# Aux_Power_Board_V2_1.net
KiCad netlist of a schematic drawn in EAGLE
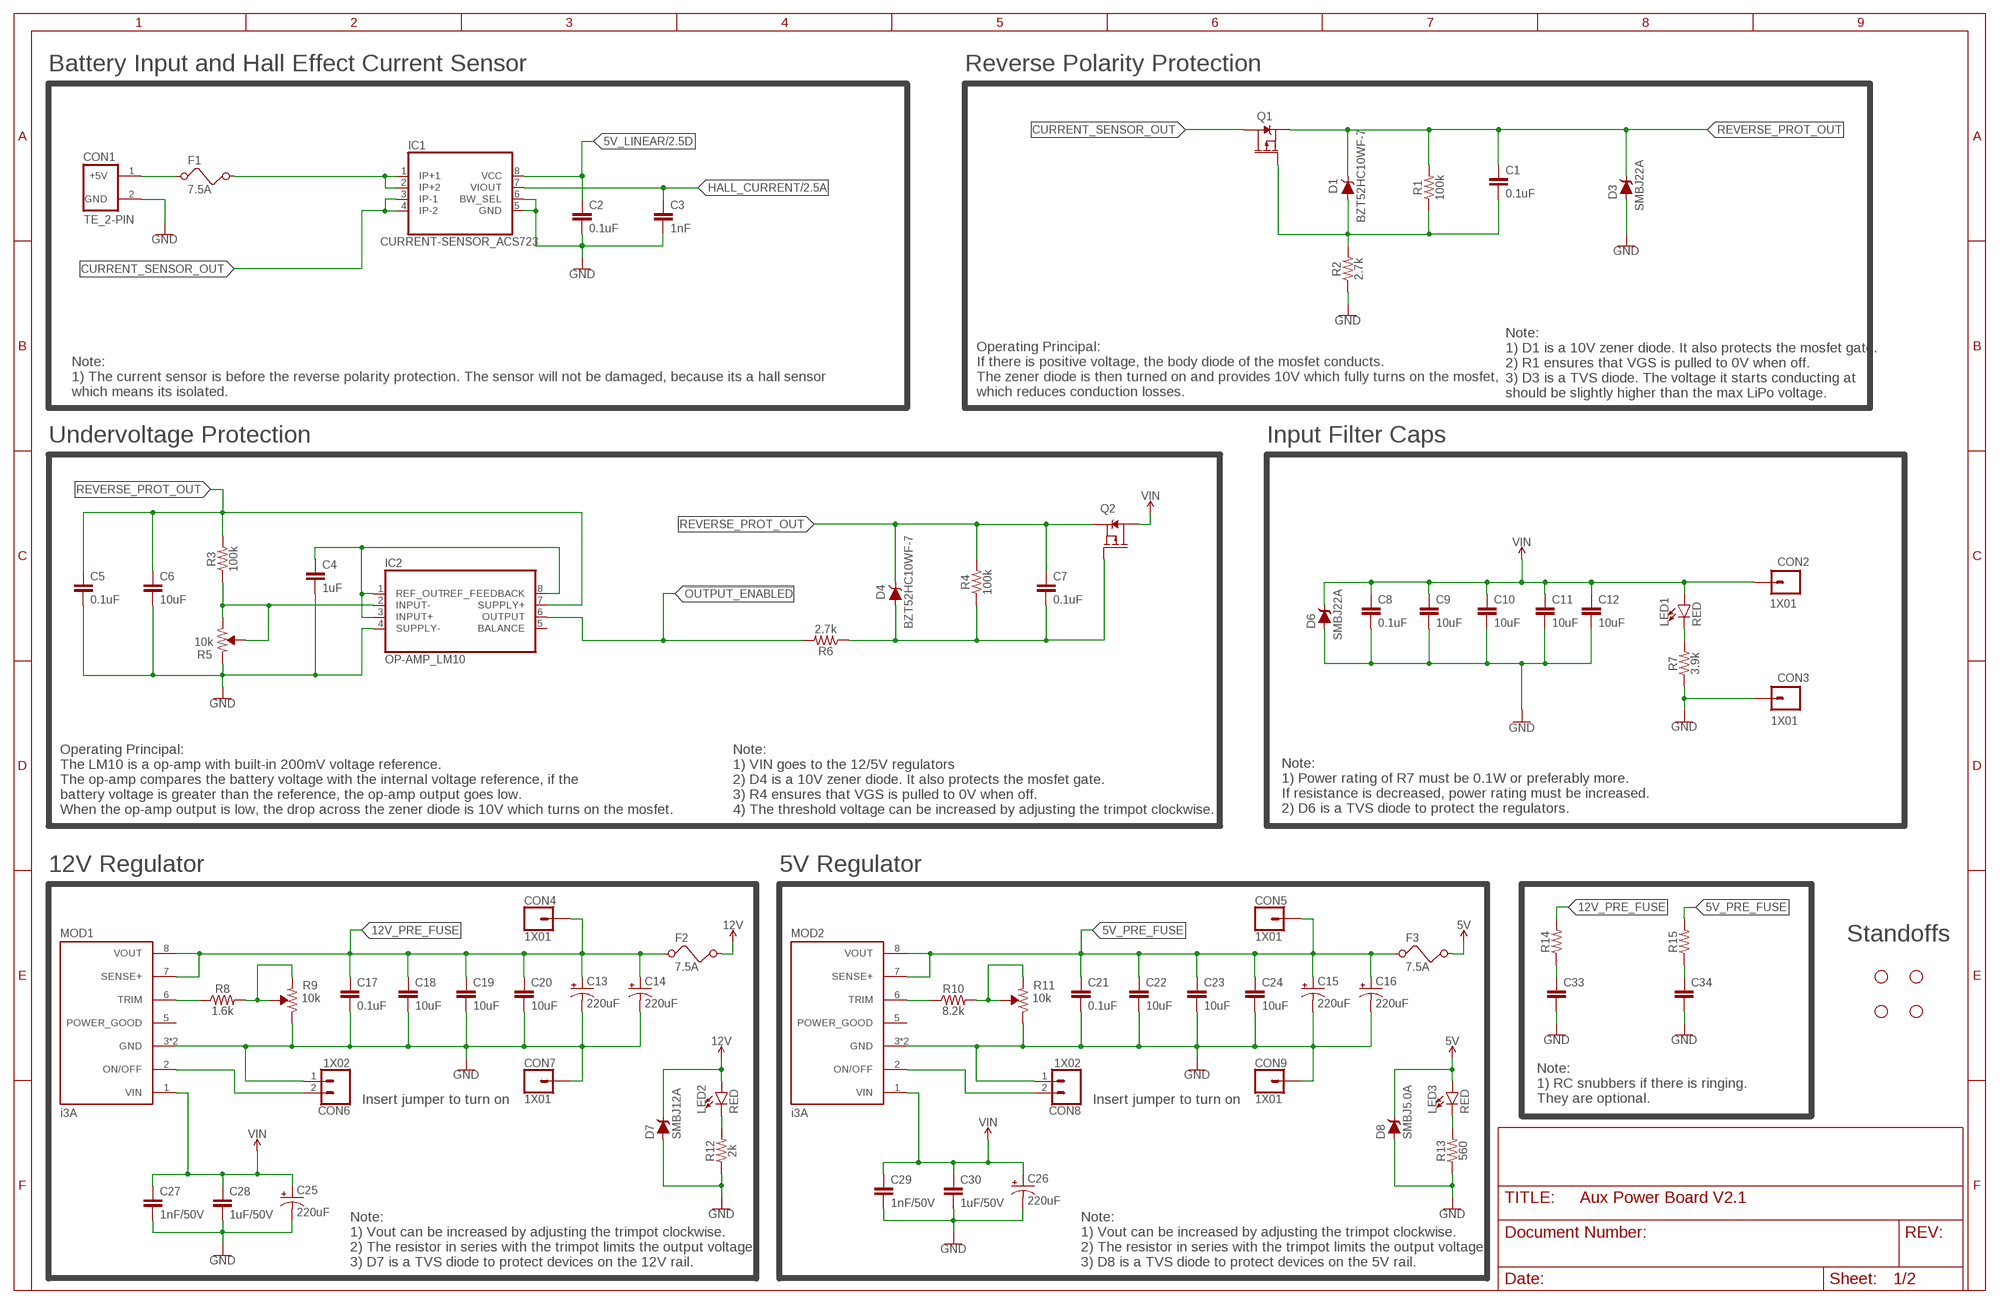
[diagram p0: schematic, sheet 1]
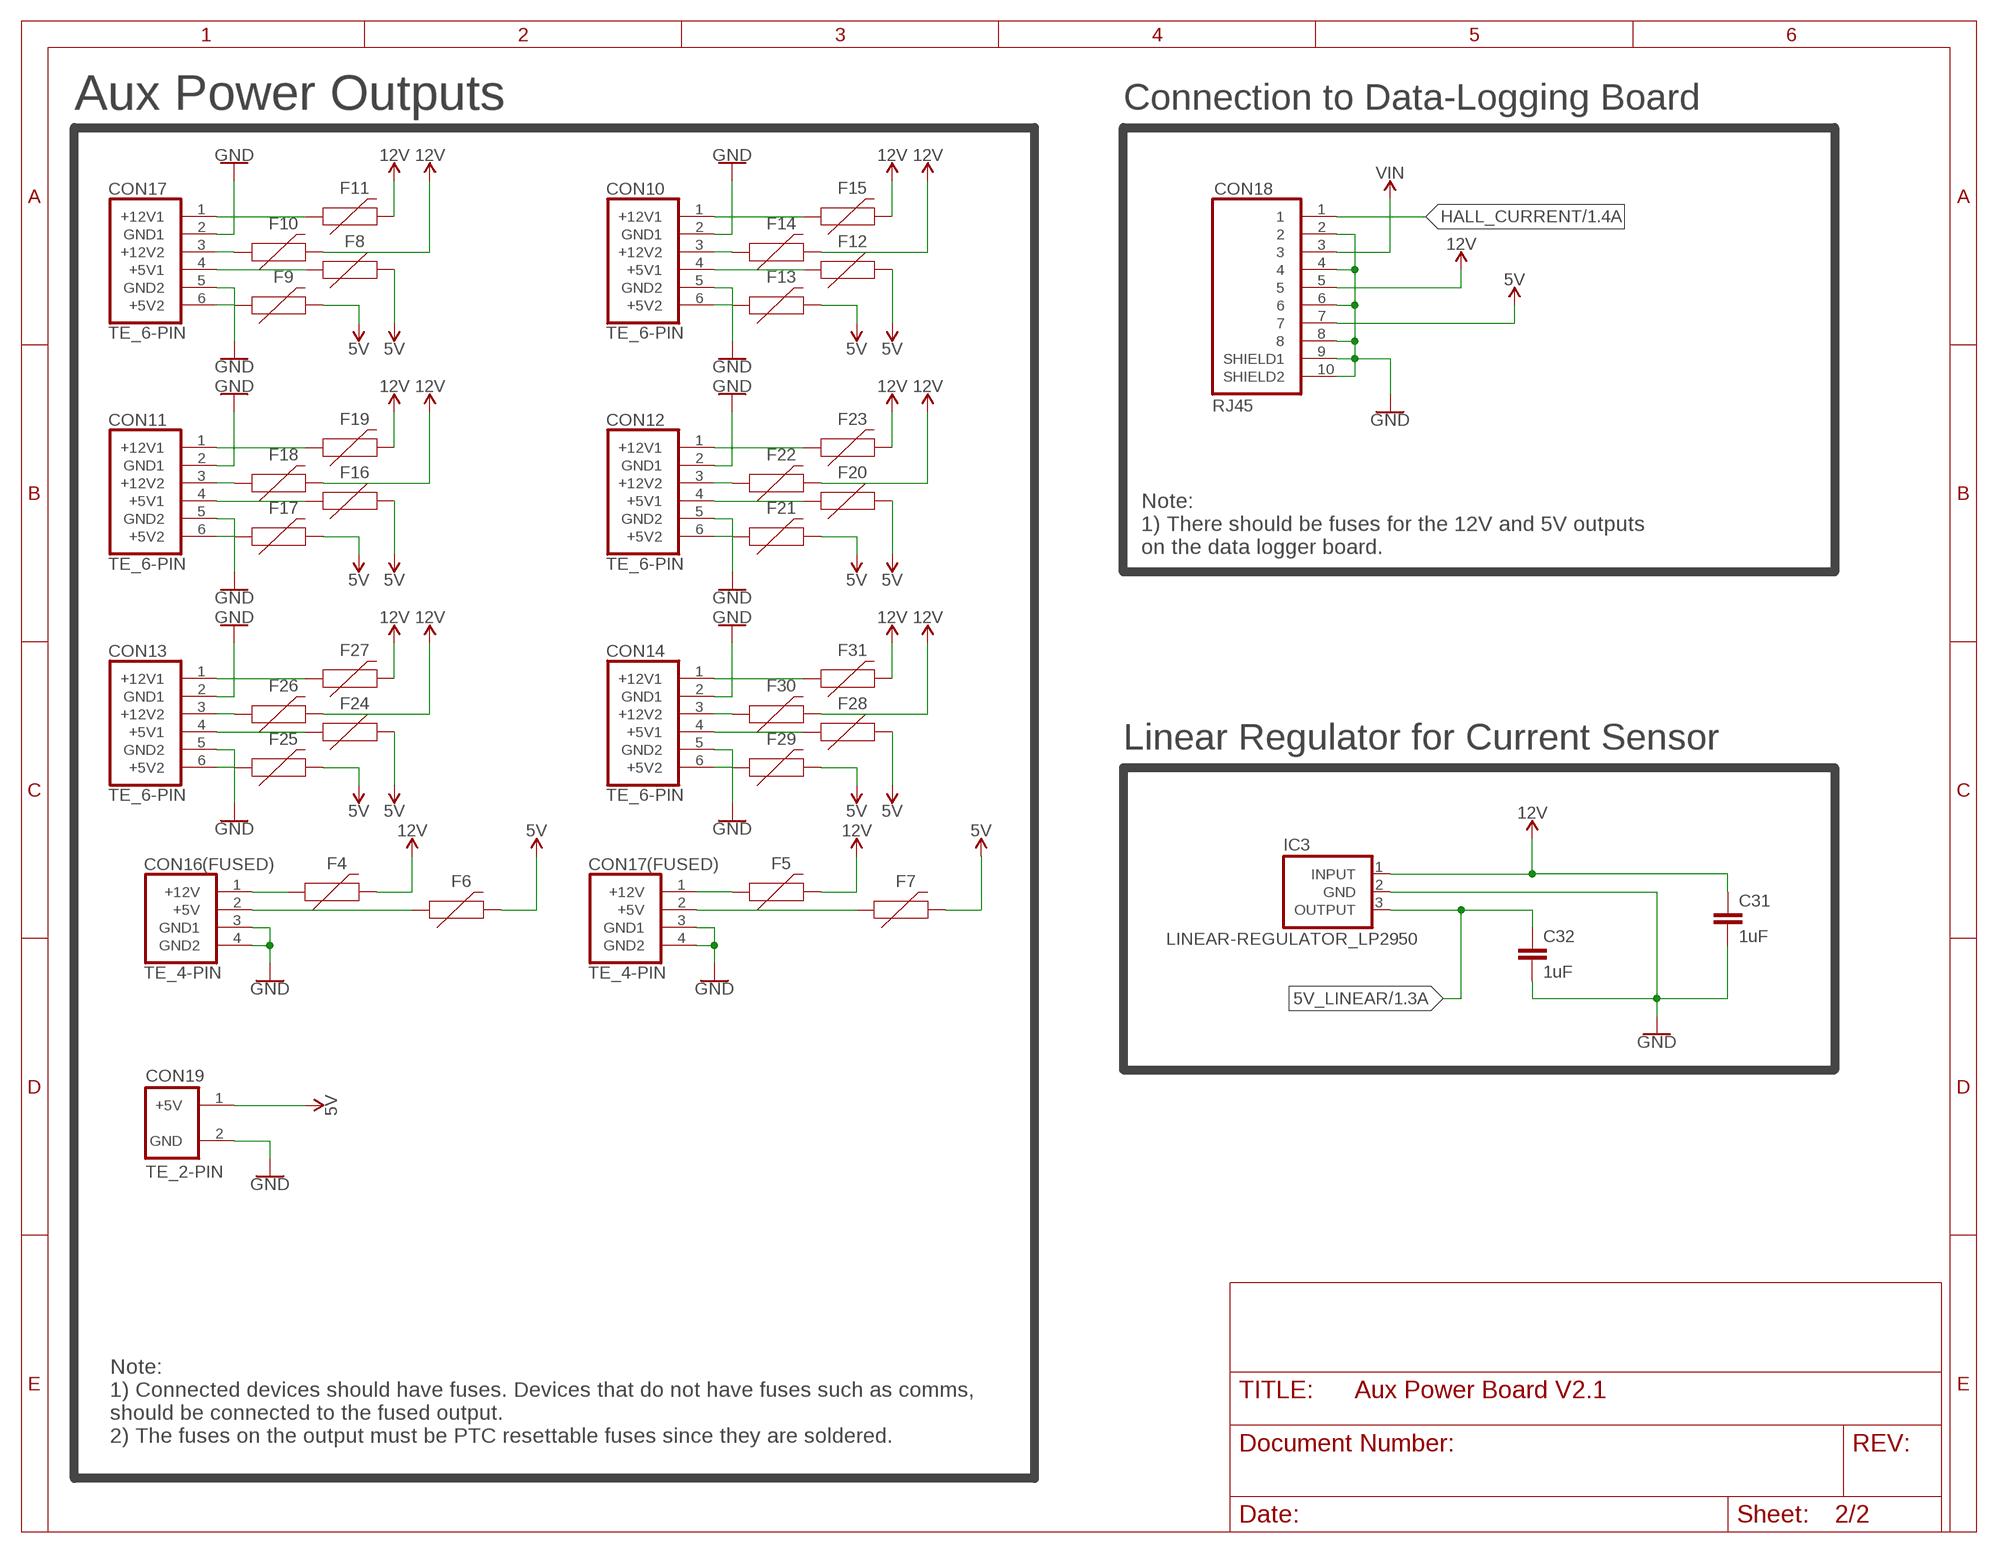
[diagram p1: schematic, sheet 2]

(export (version "E")
  (design (tool "Eeschema 10.0.6"))
  (components
    (comp (ref "C31")
      (value "1uF")
      (footprint "eagle-import:0805")
      (libsource (lib "eagle-import") (part "CAPACITOR_0805"))
    )
    (comp (ref "C32")
      (value "1uF")
      (footprint "eagle-import:0805")
      (libsource (lib "eagle-import") (part "CAPACITOR_0805"))
    )
    (comp (ref "CON10")
      (value "TE_6-PIN")
      (footprint "eagle-import:TE_6-PIN")
      (libsource (lib "eagle-import") (part "TE_6-PIN"))
    )
    (comp (ref "CON11")
      (value "TE_6-PIN")
      (footprint "eagle-import:TE_6-PIN")
      (libsource (lib "eagle-import") (part "TE_6-PIN"))
    )
    (comp (ref "CON12")
      (value "TE_6-PIN")
      (footprint "eagle-import:TE_6-PIN")
      (libsource (lib "eagle-import") (part "TE_6-PIN"))
    )
    (comp (ref "CON13")
      (value "TE_6-PIN")
      (footprint "eagle-import:TE_6-PIN")
      (libsource (lib "eagle-import") (part "TE_6-PIN"))
    )
    (comp (ref "CON14")
      (value "TE_6-PIN")
      (footprint "eagle-import:TE_6-PIN")
      (libsource (lib "eagle-import") (part "TE_6-PIN"))
    )
    (comp (ref "CON16(FUSED)")
      (value "TE_4-PIN")
      (footprint "eagle-import:TE_4-PIN")
      (libsource (lib "eagle-import") (part "TE_4-PIN"))
    )
    (comp (ref "CON17")
      (value "TE_6-PIN")
      (footprint "eagle-import:TE_6-PIN")
      (libsource (lib "eagle-import") (part "TE_6-PIN"))
    )
    (comp (ref "CON17(FUSED)")
      (value "TE_4-PIN")
      (footprint "eagle-import:TE_4-PIN")
      (libsource (lib "eagle-import") (part "TE_4-PIN"))
    )
    (comp (ref "CON18")
      (value "RJ45")
      (footprint "eagle-import:RJ45")
      (libsource (lib "eagle-import") (part "RJ45"))
    )
    (comp (ref "CON19")
      (value "TE_2-PIN")
      (footprint "eagle-import:TE_2-PIN")
      (libsource (lib "eagle-import") (part "TE_2-PIN"))
    )
    (comp (ref "F4")
      (value "FUSE_1210_RESETTABLE")
      (footprint "eagle-import:1210")
      (libsource (lib "eagle-import") (part "FUSE_1210_RESETTABLE"))
    )
    (comp (ref "F5")
      (value "FUSE_1210_RESETTABLE")
      (footprint "eagle-import:1210")
      (libsource (lib "eagle-import") (part "FUSE_1210_RESETTABLE"))
    )
    (comp (ref "F6")
      (value "FUSE_1210_RESETTABLE")
      (footprint "eagle-import:1210")
      (libsource (lib "eagle-import") (part "FUSE_1210_RESETTABLE"))
    )
    (comp (ref "F7")
      (value "FUSE_1210_RESETTABLE")
      (footprint "eagle-import:1210")
      (libsource (lib "eagle-import") (part "FUSE_1210_RESETTABLE"))
    )
    (comp (ref "F8")
      (value "FUSE_1210_RESETTABLE")
      (footprint "eagle-import:1210")
      (libsource (lib "eagle-import") (part "FUSE_1210_RESETTABLE"))
    )
    (comp (ref "F9")
      (value "FUSE_1210_RESETTABLE")
      (footprint "eagle-import:1210")
      (libsource (lib "eagle-import") (part "FUSE_1210_RESETTABLE"))
    )
    (comp (ref "F10")
      (value "FUSE_1210_RESETTABLE")
      (footprint "eagle-import:1210")
      (libsource (lib "eagle-import") (part "FUSE_1210_RESETTABLE"))
    )
    (comp (ref "F11")
      (value "FUSE_1210_RESETTABLE")
      (footprint "eagle-import:1210")
      (libsource (lib "eagle-import") (part "FUSE_1210_RESETTABLE"))
    )
    (comp (ref "F12")
      (value "FUSE_1210_RESETTABLE")
      (footprint "eagle-import:1210")
      (libsource (lib "eagle-import") (part "FUSE_1210_RESETTABLE"))
    )
    (comp (ref "F13")
      (value "FUSE_1210_RESETTABLE")
      (footprint "eagle-import:1210")
      (libsource (lib "eagle-import") (part "FUSE_1210_RESETTABLE"))
    )
    (comp (ref "F14")
      (value "FUSE_1210_RESETTABLE")
      (footprint "eagle-import:1210")
      (libsource (lib "eagle-import") (part "FUSE_1210_RESETTABLE"))
    )
    (comp (ref "F15")
      (value "FUSE_1210_RESETTABLE")
      (footprint "eagle-import:1210")
      (libsource (lib "eagle-import") (part "FUSE_1210_RESETTABLE"))
    )
    (comp (ref "F16")
      (value "FUSE_1210_RESETTABLE")
      (footprint "eagle-import:1210")
      (libsource (lib "eagle-import") (part "FUSE_1210_RESETTABLE"))
    )
    (comp (ref "F17")
      (value "FUSE_1210_RESETTABLE")
      (footprint "eagle-import:1210")
      (libsource (lib "eagle-import") (part "FUSE_1210_RESETTABLE"))
    )
    (comp (ref "F18")
      (value "FUSE_1210_RESETTABLE")
      (footprint "eagle-import:1210")
      (libsource (lib "eagle-import") (part "FUSE_1210_RESETTABLE"))
    )
    (comp (ref "F19")
      (value "FUSE_1210_RESETTABLE")
      (footprint "eagle-import:1210")
      (libsource (lib "eagle-import") (part "FUSE_1210_RESETTABLE"))
    )
    (comp (ref "F20")
      (value "FUSE_1210_RESETTABLE")
      (footprint "eagle-import:1210")
      (libsource (lib "eagle-import") (part "FUSE_1210_RESETTABLE"))
    )
    (comp (ref "F21")
      (value "FUSE_1210_RESETTABLE")
      (footprint "eagle-import:1210")
      (libsource (lib "eagle-import") (part "FUSE_1210_RESETTABLE"))
    )
    (comp (ref "F22")
      (value "FUSE_1210_RESETTABLE")
      (footprint "eagle-import:1210")
      (libsource (lib "eagle-import") (part "FUSE_1210_RESETTABLE"))
    )
    (comp (ref "F23")
      (value "FUSE_1210_RESETTABLE")
      (footprint "eagle-import:1210")
      (libsource (lib "eagle-import") (part "FUSE_1210_RESETTABLE"))
    )
    (comp (ref "F24")
      (value "FUSE_1210_RESETTABLE")
      (footprint "eagle-import:1210")
      (libsource (lib "eagle-import") (part "FUSE_1210_RESETTABLE"))
    )
    (comp (ref "F25")
      (value "FUSE_1210_RESETTABLE")
      (footprint "eagle-import:1210")
      (libsource (lib "eagle-import") (part "FUSE_1210_RESETTABLE"))
    )
    (comp (ref "F26")
      (value "FUSE_1210_RESETTABLE")
      (footprint "eagle-import:1210")
      (libsource (lib "eagle-import") (part "FUSE_1210_RESETTABLE"))
    )
    (comp (ref "F27")
      (value "FUSE_1210_RESETTABLE")
      (footprint "eagle-import:1210")
      (libsource (lib "eagle-import") (part "FUSE_1210_RESETTABLE"))
    )
    (comp (ref "F28")
      (value "FUSE_1210_RESETTABLE")
      (footprint "eagle-import:1210")
      (libsource (lib "eagle-import") (part "FUSE_1210_RESETTABLE"))
    )
    (comp (ref "F29")
      (value "FUSE_1210_RESETTABLE")
      (footprint "eagle-import:1210")
      (libsource (lib "eagle-import") (part "FUSE_1210_RESETTABLE"))
    )
    (comp (ref "F30")
      (value "FUSE_1210_RESETTABLE")
      (footprint "eagle-import:1210")
      (libsource (lib "eagle-import") (part "FUSE_1210_RESETTABLE"))
    )
    (comp (ref "F31")
      (value "FUSE_1210_RESETTABLE")
      (footprint "eagle-import:1210")
      (libsource (lib "eagle-import") (part "FUSE_1210_RESETTABLE"))
    )
    (comp (ref "IC3")
      (value "LINEAR-REGULATOR_LP2950")
      (footprint "eagle-import:TO92")
      (libsource (lib "eagle-import") (part "LINEAR-REGULATOR_LP2950"))
    )
    (comp (ref "C1")
      (value "0.1uF")
      (footprint "eagle-import:0805")
      (libsource (lib "eagle-import") (part "CAPACITOR_0805"))
    )
    (comp (ref "C2")
      (value "0.1uF")
      (footprint "eagle-import:0805")
      (libsource (lib "eagle-import") (part "CAPACITOR_0805"))
    )
    (comp (ref "C3")
      (value "1nF")
      (footprint "eagle-import:0805")
      (libsource (lib "eagle-import") (part "CAPACITOR_0805"))
    )
    (comp (ref "C4")
      (value "1uF")
      (footprint "eagle-import:0805")
      (libsource (lib "eagle-import") (part "CAPACITOR_0805"))
    )
    (comp (ref "C5")
      (value "0.1uF")
      (footprint "eagle-import:0805")
      (libsource (lib "eagle-import") (part "CAPACITOR_0805"))
    )
    (comp (ref "C6")
      (value "10uF")
      (footprint "eagle-import:1210")
      (libsource (lib "eagle-import") (part "CAPACITOR_1210"))
    )
    (comp (ref "C7")
      (value "0.1uF")
      (footprint "eagle-import:0805")
      (libsource (lib "eagle-import") (part "CAPACITOR_0805"))
    )
    (comp (ref "C8")
      (value "0.1uF")
      (footprint "eagle-import:0805")
      (libsource (lib "eagle-import") (part "CAPACITOR_0805"))
    )
    (comp (ref "C9")
      (value "10uF")
      (footprint "eagle-import:1210")
      (libsource (lib "eagle-import") (part "CAPACITOR_1210"))
    )
    (comp (ref "C10")
      (value "10uF")
      (footprint "eagle-import:1210")
      (libsource (lib "eagle-import") (part "CAPACITOR_1210"))
    )
    (comp (ref "C11")
      (value "10uF")
      (footprint "eagle-import:1210")
      (libsource (lib "eagle-import") (part "CAPACITOR_1210"))
    )
    (comp (ref "C12")
      (value "10uF")
      (footprint "eagle-import:1210")
      (libsource (lib "eagle-import") (part "CAPACITOR_1210"))
    )
    (comp (ref "C13")
      (value "220uF")
      (footprint "eagle-import:CAPACITOR_220UF_63V")
      (libsource (lib "eagle-import") (part "CAPACITOR_ELECTROLYTIC_220UF"))
    )
    (comp (ref "C14")
      (value "220uF")
      (footprint "eagle-import:CAPACITOR_220UF_63V")
      (libsource (lib "eagle-import") (part "CAPACITOR_ELECTROLYTIC_220UF"))
    )
    (comp (ref "C15")
      (value "220uF")
      (footprint "eagle-import:CAPACITOR_220UF_63V")
      (libsource (lib "eagle-import") (part "CAPACITOR_ELECTROLYTIC_220UF"))
    )
    (comp (ref "C16")
      (value "220uF")
      (footprint "eagle-import:CAPACITOR_220UF_63V")
      (libsource (lib "eagle-import") (part "CAPACITOR_ELECTROLYTIC_220UF"))
    )
    (comp (ref "C17")
      (value "0.1uF")
      (footprint "eagle-import:0805")
      (libsource (lib "eagle-import") (part "CAPACITOR_0805"))
    )
    (comp (ref "C18")
      (value "10uF")
      (footprint "eagle-import:0805")
      (libsource (lib "eagle-import") (part "CAPACITOR_0805"))
    )
    (comp (ref "C19")
      (value "10uF")
      (footprint "eagle-import:0805")
      (libsource (lib "eagle-import") (part "CAPACITOR_0805"))
    )
    (comp (ref "C20")
      (value "10uF")
      (footprint "eagle-import:0805")
      (libsource (lib "eagle-import") (part "CAPACITOR_0805"))
    )
    (comp (ref "C21")
      (value "0.1uF")
      (footprint "eagle-import:0805")
      (libsource (lib "eagle-import") (part "CAPACITOR_0805"))
    )
    (comp (ref "C22")
      (value "10uF")
      (footprint "eagle-import:0805")
      (libsource (lib "eagle-import") (part "CAPACITOR_0805"))
    )
    (comp (ref "C23")
      (value "10uF")
      (footprint "eagle-import:0805")
      (libsource (lib "eagle-import") (part "CAPACITOR_0805"))
    )
    (comp (ref "C24")
      (value "10uF")
      (footprint "eagle-import:0805")
      (libsource (lib "eagle-import") (part "CAPACITOR_0805"))
    )
    (comp (ref "C25")
      (value "220uF")
      (footprint "eagle-import:CAPACITOR_220UF_63V")
      (libsource (lib "eagle-import") (part "CAPACITOR_ELECTROLYTIC_220UF"))
    )
    (comp (ref "C26")
      (value "220uF")
      (footprint "eagle-import:CAPACITOR_220UF_63V")
      (libsource (lib "eagle-import") (part "CAPACITOR_ELECTROLYTIC_220UF"))
    )
    (comp (ref "C27")
      (value "1nF/50V")
      (footprint "eagle-import:0805")
      (libsource (lib "eagle-import") (part "CAPACITOR_0805"))
    )
    (comp (ref "C28")
      (value "1uF/50V")
      (footprint "eagle-import:0805")
      (libsource (lib "eagle-import") (part "CAPACITOR_0805"))
    )
    (comp (ref "C29")
      (value "1nF/50V")
      (footprint "eagle-import:0805")
      (libsource (lib "eagle-import") (part "CAPACITOR_0805"))
    )
    (comp (ref "C30")
      (value "1uF/50V")
      (footprint "eagle-import:0805")
      (libsource (lib "eagle-import") (part "CAPACITOR_0805"))
    )
    (comp (ref "C33")
      (value "CAPACITOR_0805")
      (footprint "eagle-import:0805")
      (libsource (lib "eagle-import") (part "CAPACITOR_0805"))
    )
    (comp (ref "C34")
      (value "CAPACITOR_0805")
      (footprint "eagle-import:0805")
      (libsource (lib "eagle-import") (part "CAPACITOR_0805"))
    )
    (comp (ref "CON1")
      (value "TE_2-PIN")
      (footprint "eagle-import:TE_2-PIN")
      (libsource (lib "eagle-import") (part "TE_2-PIN"))
    )
    (comp (ref "CON2")
      (value "1X01")
      (footprint "eagle-import:1X01")
      (libsource (lib "eagle-import") (part "1X01"))
    )
    (comp (ref "CON3")
      (value "1X01")
      (footprint "eagle-import:1X01")
      (libsource (lib "eagle-import") (part "1X01"))
    )
    (comp (ref "CON4")
      (value "1X01")
      (footprint "eagle-import:1X01")
      (libsource (lib "eagle-import") (part "1X01"))
    )
    (comp (ref "CON5")
      (value "1X01")
      (footprint "eagle-import:1X01")
      (libsource (lib "eagle-import") (part "1X01"))
    )
    (comp (ref "CON6")
      (value "1X02")
      (footprint "eagle-import:1X02")
      (libsource (lib "eagle-import") (part "1X02"))
    )
    (comp (ref "CON7")
      (value "1X01")
      (footprint "eagle-import:1X01")
      (libsource (lib "eagle-import") (part "1X01"))
    )
    (comp (ref "CON8")
      (value "1X02")
      (footprint "eagle-import:1X02")
      (libsource (lib "eagle-import") (part "1X02"))
    )
    (comp (ref "CON9")
      (value "1X01")
      (footprint "eagle-import:1X01")
      (libsource (lib "eagle-import") (part "1X01"))
    )
    (comp (ref "D1")
      (value "BZT52HC10WF-7")
      (footprint "eagle-import:SOD123FL")
      (libsource (lib "eagle-import") (part "DIODE_ZENER_SOD123F"))
    )
    (comp (ref "D3")
      (value "SMBJ22A")
      (footprint "eagle-import:DO214AA")
      (libsource (lib "eagle-import") (part "DIODE_TVS_UNI_DO-214AA"))
    )
    (comp (ref "D4")
      (value "BZT52HC10WF-7")
      (footprint "eagle-import:SOD123FL")
      (libsource (lib "eagle-import") (part "DIODE_ZENER_SOD123F"))
    )
    (comp (ref "D6")
      (value "SMBJ22A")
      (footprint "eagle-import:DO214AA")
      (libsource (lib "eagle-import") (part "DIODE_TVS_UNI_DO-214AA"))
    )
    (comp (ref "D7")
      (value "SMBJ12A")
      (footprint "eagle-import:DO214AA")
      (libsource (lib "eagle-import") (part "DIODE_TVS_UNI_DO-214AA"))
    )
    (comp (ref "D8")
      (value "SMBJ5.0A")
      (footprint "eagle-import:DO214AA")
      (libsource (lib "eagle-import") (part "DIODE_TVS_UNI_DO-214AA"))
    )
    (comp (ref "F1")
      (value "7.5A")
      (footprint "eagle-import:FUSEHOLDER_VERTICAL")
      (libsource (lib "eagle-import") (part "FUSEHOLDER_VERTICAL"))
    )
    (comp (ref "F2")
      (value "7.5A")
      (footprint "eagle-import:FUSEHOLDER_VERTICAL")
      (libsource (lib "eagle-import") (part "FUSEHOLDER_VERTICAL"))
    )
    (comp (ref "F3")
      (value "7.5A")
      (footprint "eagle-import:FUSEHOLDER_VERTICAL")
      (libsource (lib "eagle-import") (part "FUSEHOLDER_VERTICAL"))
    )
    (comp (ref "H1")
      (value "STAND-OFF")
      (footprint "eagle-import:STAND-OFF")
      (libsource (lib "eagle-import") (part "STAND-OFF"))
    )
    (comp (ref "H2")
      (value "STAND-OFF")
      (footprint "eagle-import:STAND-OFF")
      (libsource (lib "eagle-import") (part "STAND-OFF"))
    )
    (comp (ref "H3")
      (value "STAND-OFF")
      (footprint "eagle-import:STAND-OFF")
      (libsource (lib "eagle-import") (part "STAND-OFF"))
    )
    (comp (ref "H4")
      (value "STAND-OFF")
      (footprint "eagle-import:STAND-OFF")
      (libsource (lib "eagle-import") (part "STAND-OFF"))
    )
    (comp (ref "IC1")
      (value "CURRENT-SENSOR_ACS723")
      (footprint "eagle-import:SOIC8")
      (libsource (lib "eagle-import") (part "CURRENT-SENSOR_ACS723"))
    )
    (comp (ref "IC2")
      (value "OP-AMP_LM10")
      (footprint "eagle-import:DIP08")
      (libsource (lib "eagle-import") (part "OP-AMP_LM10"))
    )
    (comp (ref "LED1")
      (value "RED")
      (footprint "eagle-import:0805_LED")
      (libsource (lib "eagle-import") (part "LED_0805"))
    )
    (comp (ref "LED2")
      (value "RED")
      (footprint "eagle-import:0805_LED")
      (libsource (lib "eagle-import") (part "LED_0805"))
    )
    (comp (ref "LED3")
      (value "RED")
      (footprint "eagle-import:0805_LED")
      (libsource (lib "eagle-import") (part "LED_0805"))
    )
    (comp (ref "MOD1")
      (value "i3A")
      (footprint "eagle-import:CONVERTER_I3A")
      (libsource (lib "eagle-import") (part "CONVERTER_I3A"))
    )
    (comp (ref "MOD2")
      (value "i3A")
      (footprint "eagle-import:CONVERTER_I3A")
      (libsource (lib "eagle-import") (part "CONVERTER_I3A"))
    )
    (comp (ref "Q1")
      (value "MOSFET_PMOS_TO-263")
      (footprint "eagle-import:TO-263_D2PAK")
      (libsource (lib "eagle-import") (part "MOSFET_PMOS_TO-263"))
    )
    (comp (ref "Q2")
      (value "MOSFET_PMOS_TO-263")
      (footprint "eagle-import:TO-263_D2PAK")
      (libsource (lib "eagle-import") (part "MOSFET_PMOS_TO-263"))
    )
    (comp (ref "R1")
      (value "100k")
      (footprint "eagle-import:0805")
      (libsource (lib "eagle-import") (part "RESISTOR_0805"))
    )
    (comp (ref "R2")
      (value "2.7k")
      (footprint "eagle-import:0805")
      (libsource (lib "eagle-import") (part "RESISTOR_0805"))
    )
    (comp (ref "R3")
      (value "100k")
      (footprint "eagle-import:0805")
      (libsource (lib "eagle-import") (part "RESISTOR_0805"))
    )
    (comp (ref "R4")
      (value "100k")
      (footprint "eagle-import:0805")
      (libsource (lib "eagle-import") (part "RESISTOR_0805"))
    )
    (comp (ref "R5")
      (value "10k")
      (footprint "eagle-import:TRIMPOT")
      (libsource (lib "eagle-import") (part "RESISTOR_TRIMPOT"))
    )
    (comp (ref "R6")
      (value "2.7k")
      (footprint "eagle-import:0805")
      (libsource (lib "eagle-import") (part "RESISTOR_0805"))
    )
    (comp (ref "R7")
      (value "3.9k")
      (footprint "eagle-import:0805")
      (libsource (lib "eagle-import") (part "RESISTOR_0805"))
    )
    (comp (ref "R8")
      (value "1.6k")
      (footprint "eagle-import:0805")
      (libsource (lib "eagle-import") (part "RESISTOR_0805"))
    )
    (comp (ref "R9")
      (value "10k")
      (footprint "eagle-import:TRIMPOT")
      (libsource (lib "eagle-import") (part "RESISTOR_TRIMPOT"))
    )
    (comp (ref "R10")
      (value "8.2k")
      (footprint "eagle-import:0805")
      (libsource (lib "eagle-import") (part "RESISTOR_0805"))
    )
    (comp (ref "R11")
      (value "10k")
      (footprint "eagle-import:TRIMPOT")
      (libsource (lib "eagle-import") (part "RESISTOR_TRIMPOT"))
    )
    (comp (ref "R12")
      (value "2k")
      (footprint "eagle-import:0805")
      (libsource (lib "eagle-import") (part "RESISTOR_0805"))
    )
    (comp (ref "R13")
      (value "560")
      (footprint "eagle-import:0805")
      (libsource (lib "eagle-import") (part "RESISTOR_0805"))
    )
    (comp (ref "R14")
      (value "RESISTOR_0805")
      (footprint "eagle-import:0805")
      (libsource (lib "eagle-import") (part "RESISTOR_0805"))
    )
    (comp (ref "R15")
      (value "RESISTOR_0805")
      (footprint "eagle-import:0805")
      (libsource (lib "eagle-import") (part "RESISTOR_0805"))
    )
  )
  (nets
    (net (code "1") (name "5V") (class "Default")
      (node (ref "CON18") (pin "7") (pinfunction "7_7") (pintype "passive"))
      (node (ref "CON19") (pin "1") (pinfunction "+5V_1") (pintype "passive"))
      (node (ref "D8") (pin "C") (pinfunction "C_C") (pintype "passive"))
      (node (ref "F12") (pin "2") (pinfunction "2_2") (pintype "bidirectional"))
      (node (ref "F13") (pin "2") (pinfunction "2_2") (pintype "bidirectional"))
      (node (ref "F16") (pin "2") (pinfunction "2_2") (pintype "bidirectional"))
      (node (ref "F17") (pin "2") (pinfunction "2_2") (pintype "bidirectional"))
      (node (ref "F20") (pin "2") (pinfunction "2_2") (pintype "bidirectional"))
      (node (ref "F21") (pin "2") (pinfunction "2_2") (pintype "bidirectional"))
      (node (ref "F24") (pin "2") (pinfunction "2_2") (pintype "bidirectional"))
      (node (ref "F25") (pin "2") (pinfunction "2_2") (pintype "bidirectional"))
      (node (ref "F28") (pin "2") (pinfunction "2_2") (pintype "bidirectional"))
      (node (ref "F29") (pin "2") (pinfunction "2_2") (pintype "bidirectional"))
      (node (ref "F3") (pin "3") (pinfunction "2_3") (pintype "passive"))
      (node (ref "F3") (pin "4") (pinfunction "2_4") (pintype "passive"))
      (node (ref "F6") (pin "2") (pinfunction "2_2") (pintype "bidirectional"))
      (node (ref "F7") (pin "2") (pinfunction "2_2") (pintype "bidirectional"))
      (node (ref "F8") (pin "2") (pinfunction "2_2") (pintype "bidirectional"))
      (node (ref "F9") (pin "2") (pinfunction "2_2") (pintype "bidirectional"))
      (node (ref "LED3") (pin "1") (pinfunction "A_1") (pintype "passive"))
    )
    (net (code "2") (name "5V_LINEAR") (class "Default")
      (node (ref "C2") (pin "1") (pinfunction "1_1") (pintype "passive"))
      (node (ref "C32") (pin "1") (pinfunction "1_1") (pintype "passive"))
      (node (ref "IC1") (pin "8") (pinfunction "VCC_8") (pintype "bidirectional"))
      (node (ref "IC3") (pin "3") (pinfunction "OUTPUT_3") (pintype "bidirectional"))
    )
    (net (code "3") (name "5V_PRE_FUSE") (class "Default")
      (node (ref "C15") (pin "+") (pinfunction "+_+") (pintype "passive"))
      (node (ref "C16") (pin "+") (pinfunction "+_+") (pintype "passive"))
      (node (ref "C21") (pin "1") (pinfunction "1_1") (pintype "passive"))
      (node (ref "C22") (pin "1") (pinfunction "1_1") (pintype "passive"))
      (node (ref "C23") (pin "1") (pinfunction "1_1") (pintype "passive"))
      (node (ref "C24") (pin "1") (pinfunction "1_1") (pintype "passive"))
      (node (ref "CON5") (pin "1") (pinfunction "1_1") (pintype "passive"))
      (node (ref "F3") (pin "1") (pinfunction "1_1") (pintype "passive"))
      (node (ref "F3") (pin "2") (pinfunction "1_2") (pintype "passive"))
      (node (ref "MOD2") (pin "7") (pinfunction "SENSE+_7") (pintype "bidirectional"))
      (node (ref "MOD2") (pin "8") (pinfunction "VOUT_8") (pintype "bidirectional"))
      (node (ref "R15") (pin "2") (pinfunction "2_2") (pintype "passive"))
    )
    (net (code "4") (name "12V") (class "Default")
      (node (ref "C31") (pin "1") (pinfunction "1_1") (pintype "passive"))
      (node (ref "CON18") (pin "5") (pinfunction "5_5") (pintype "passive"))
      (node (ref "D7") (pin "C") (pinfunction "C_C") (pintype "passive"))
      (node (ref "F10") (pin "2") (pinfunction "2_2") (pintype "bidirectional"))
      (node (ref "F11") (pin "2") (pinfunction "2_2") (pintype "bidirectional"))
      (node (ref "F14") (pin "2") (pinfunction "2_2") (pintype "bidirectional"))
      (node (ref "F15") (pin "2") (pinfunction "2_2") (pintype "bidirectional"))
      (node (ref "F18") (pin "2") (pinfunction "2_2") (pintype "bidirectional"))
      (node (ref "F19") (pin "2") (pinfunction "2_2") (pintype "bidirectional"))
      (node (ref "F2") (pin "3") (pinfunction "2_3") (pintype "passive"))
      (node (ref "F2") (pin "4") (pinfunction "2_4") (pintype "passive"))
      (node (ref "F22") (pin "2") (pinfunction "2_2") (pintype "bidirectional"))
      (node (ref "F23") (pin "2") (pinfunction "2_2") (pintype "bidirectional"))
      (node (ref "F26") (pin "2") (pinfunction "2_2") (pintype "bidirectional"))
      (node (ref "F27") (pin "2") (pinfunction "2_2") (pintype "bidirectional"))
      (node (ref "F30") (pin "2") (pinfunction "2_2") (pintype "bidirectional"))
      (node (ref "F31") (pin "2") (pinfunction "2_2") (pintype "bidirectional"))
      (node (ref "F4") (pin "2") (pinfunction "2_2") (pintype "bidirectional"))
      (node (ref "F5") (pin "2") (pinfunction "2_2") (pintype "bidirectional"))
      (node (ref "IC3") (pin "1") (pinfunction "INPUT_1") (pintype "bidirectional"))
      (node (ref "LED2") (pin "1") (pinfunction "A_1") (pintype "passive"))
    )
    (net (code "5") (name "12V_PRE_FUSE") (class "Default")
      (node (ref "C13") (pin "+") (pinfunction "+_+") (pintype "passive"))
      (node (ref "C14") (pin "+") (pinfunction "+_+") (pintype "passive"))
      (node (ref "C17") (pin "1") (pinfunction "1_1") (pintype "passive"))
      (node (ref "C18") (pin "1") (pinfunction "1_1") (pintype "passive"))
      (node (ref "C19") (pin "1") (pinfunction "1_1") (pintype "passive"))
      (node (ref "C20") (pin "1") (pinfunction "1_1") (pintype "passive"))
      (node (ref "CON4") (pin "1") (pinfunction "1_1") (pintype "passive"))
      (node (ref "F2") (pin "1") (pinfunction "1_1") (pintype "passive"))
      (node (ref "F2") (pin "2") (pinfunction "1_2") (pintype "passive"))
      (node (ref "MOD1") (pin "7") (pinfunction "SENSE+_7") (pintype "bidirectional"))
      (node (ref "MOD1") (pin "8") (pinfunction "VOUT_8") (pintype "bidirectional"))
      (node (ref "R14") (pin "2") (pinfunction "2_2") (pintype "passive"))
    )
    (net (code "6") (name "CURRENT_SENSOR_OUT") (class "Default")
      (node (ref "IC1") (pin "3") (pinfunction "IP-1_3") (pintype "bidirectional"))
      (node (ref "IC1") (pin "4") (pinfunction "IP-2_4") (pintype "bidirectional"))
      (node (ref "Q1") (pin "2") (pinfunction "D_2") (pintype "bidirectional"))
    )
    (net (code "7") (name "GND") (class "Default")
      (node (ref "C10") (pin "2") (pinfunction "2_2") (pintype "passive"))
      (node (ref "C11") (pin "2") (pinfunction "2_2") (pintype "passive"))
      (node (ref "C12") (pin "2") (pinfunction "2_2") (pintype "passive"))
      (node (ref "C13") (pin "-") (pinfunction "-_-") (pintype "passive"))
      (node (ref "C14") (pin "-") (pinfunction "-_-") (pintype "passive"))
      (node (ref "C15") (pin "-") (pinfunction "-_-") (pintype "passive"))
      (node (ref "C16") (pin "-") (pinfunction "-_-") (pintype "passive"))
      (node (ref "C17") (pin "2") (pinfunction "2_2") (pintype "passive"))
      (node (ref "C18") (pin "2") (pinfunction "2_2") (pintype "passive"))
      (node (ref "C19") (pin "2") (pinfunction "2_2") (pintype "passive"))
      (node (ref "C2") (pin "2") (pinfunction "2_2") (pintype "passive"))
      (node (ref "C20") (pin "2") (pinfunction "2_2") (pintype "passive"))
      (node (ref "C21") (pin "2") (pinfunction "2_2") (pintype "passive"))
      (node (ref "C22") (pin "2") (pinfunction "2_2") (pintype "passive"))
      (node (ref "C23") (pin "2") (pinfunction "2_2") (pintype "passive"))
      (node (ref "C24") (pin "2") (pinfunction "2_2") (pintype "passive"))
      (node (ref "C25") (pin "-") (pinfunction "-_-") (pintype "passive"))
      (node (ref "C26") (pin "-") (pinfunction "-_-") (pintype "passive"))
      (node (ref "C27") (pin "2") (pinfunction "2_2") (pintype "passive"))
      (node (ref "C28") (pin "2") (pinfunction "2_2") (pintype "passive"))
      (node (ref "C29") (pin "2") (pinfunction "2_2") (pintype "passive"))
      (node (ref "C3") (pin "2") (pinfunction "2_2") (pintype "passive"))
      (node (ref "C30") (pin "2") (pinfunction "2_2") (pintype "passive"))
      (node (ref "C31") (pin "2") (pinfunction "2_2") (pintype "passive"))
      (node (ref "C32") (pin "2") (pinfunction "2_2") (pintype "passive"))
      (node (ref "C33") (pin "2") (pinfunction "2_2") (pintype "passive"))
      (node (ref "C34") (pin "2") (pinfunction "2_2") (pintype "passive"))
      (node (ref "C4") (pin "2") (pinfunction "2_2") (pintype "passive"))
      (node (ref "C5") (pin "2") (pinfunction "2_2") (pintype "passive"))
      (node (ref "C6") (pin "2") (pinfunction "2_2") (pintype "passive"))
      (node (ref "C8") (pin "2") (pinfunction "2_2") (pintype "passive"))
      (node (ref "C9") (pin "2") (pinfunction "2_2") (pintype "passive"))
      (node (ref "CON1") (pin "2") (pinfunction "GND_2") (pintype "passive"))
      (node (ref "CON10") (pin "2") (pinfunction "GND1_2") (pintype "passive"))
      (node (ref "CON10") (pin "5") (pinfunction "GND2_5") (pintype "passive"))
      (node (ref "CON11") (pin "2") (pinfunction "GND1_2") (pintype "passive"))
      (node (ref "CON11") (pin "5") (pinfunction "GND2_5") (pintype "passive"))
      (node (ref "CON12") (pin "2") (pinfunction "GND1_2") (pintype "passive"))
      (node (ref "CON12") (pin "5") (pinfunction "GND2_5") (pintype "passive"))
      (node (ref "CON13") (pin "2") (pinfunction "GND1_2") (pintype "passive"))
      (node (ref "CON13") (pin "5") (pinfunction "GND2_5") (pintype "passive"))
      (node (ref "CON14") (pin "2") (pinfunction "GND1_2") (pintype "passive"))
      (node (ref "CON14") (pin "5") (pinfunction "GND2_5") (pintype "passive"))
      (node (ref "CON16(FUSED)") (pin "3") (pinfunction "GND1_3") (pintype "passive"))
      (node (ref "CON16(FUSED)") (pin "4") (pinfunction "GND2_4") (pintype "passive"))
      (node (ref "CON17") (pin "2") (pinfunction "GND1_2") (pintype "passive"))
      (node (ref "CON17") (pin "5") (pinfunction "GND2_5") (pintype "passive"))
      (node (ref "CON17(FUSED)") (pin "3") (pinfunction "GND1_3") (pintype "passive"))
      (node (ref "CON17(FUSED)") (pin "4") (pinfunction "GND2_4") (pintype "passive"))
      (node (ref "CON18") (pin "10") (pinfunction "SHIELD2_10") (pintype "passive"))
      (node (ref "CON18") (pin "2") (pinfunction "2_2") (pintype "passive"))
      (node (ref "CON18") (pin "4") (pinfunction "4_4") (pintype "passive"))
      (node (ref "CON18") (pin "6") (pinfunction "6_6") (pintype "passive"))
      (node (ref "CON18") (pin "8") (pinfunction "8_8") (pintype "passive"))
      (node (ref "CON18") (pin "9") (pinfunction "SHIELD1_9") (pintype "passive"))
      (node (ref "CON19") (pin "2") (pinfunction "GND_2") (pintype "passive"))
      (node (ref "CON3") (pin "1") (pinfunction "1_1") (pintype "passive"))
      (node (ref "CON6") (pin "1") (pinfunction "1_1") (pintype "passive"))
      (node (ref "CON7") (pin "1") (pinfunction "1_1") (pintype "passive"))
      (node (ref "CON8") (pin "1") (pinfunction "1_1") (pintype "passive"))
      (node (ref "CON9") (pin "1") (pinfunction "1_1") (pintype "passive"))
      (node (ref "D3") (pin "A") (pinfunction "A_A") (pintype "passive"))
      (node (ref "D6") (pin "A") (pinfunction "A_A") (pintype "passive"))
      (node (ref "D7") (pin "A") (pinfunction "A_A") (pintype "passive"))
      (node (ref "D8") (pin "A") (pinfunction "A_A") (pintype "passive"))
      (node (ref "IC1") (pin "5") (pinfunction "GND_5") (pintype "bidirectional"))
      (node (ref "IC1") (pin "6") (pinfunction "BW_SEL_6") (pintype "bidirectional"))
      (node (ref "IC2") (pin "4") (pinfunction "SUPPLY-_4") (pintype "bidirectional"))
      (node (ref "IC3") (pin "2") (pinfunction "GND_2") (pintype "bidirectional"))
      (node (ref "MOD1") (pin "3") (pinfunction "GND_3") (pintype "bidirectional"))
      (node (ref "MOD1") (pin "4") (pinfunction "GND_4") (pintype "bidirectional"))
      (node (ref "MOD2") (pin "3") (pinfunction "GND_3") (pintype "bidirectional"))
      (node (ref "MOD2") (pin "4") (pinfunction "GND_4") (pintype "bidirectional"))
      (node (ref "R11") (pin "3") (pinfunction "CW_3") (pintype "passive"))
      (node (ref "R12") (pin "1") (pinfunction "1_1") (pintype "passive"))
      (node (ref "R13") (pin "1") (pinfunction "1_1") (pintype "passive"))
      (node (ref "R2") (pin "1") (pinfunction "1_1") (pintype "passive"))
      (node (ref "R5") (pin "1") (pinfunction "CCW_1") (pintype "passive"))
      (node (ref "R7") (pin "1") (pinfunction "1_1") (pintype "passive"))
      (node (ref "R9") (pin "3") (pinfunction "CW_3") (pintype "passive"))
    )
    (net (code "8") (name "HALL_CURRENT") (class "Default")
      (node (ref "C3") (pin "1") (pinfunction "1_1") (pintype "passive"))
      (node (ref "CON18") (pin "1") (pinfunction "1_1") (pintype "passive"))
      (node (ref "IC1") (pin "7") (pinfunction "VIOUT_7") (pintype "bidirectional"))
    )
    (net (code "9") (name "Net-(C33-Pad1)") (class "Default")
      (node (ref "C33") (pin "1") (pinfunction "1_1") (pintype "passive"))
      (node (ref "R14") (pin "1") (pinfunction "1_1") (pintype "passive"))
    )
    (net (code "10") (name "Net-(C34-Pad1)") (class "Default")
      (node (ref "C34") (pin "1") (pinfunction "1_1") (pintype "passive"))
      (node (ref "R15") (pin "1") (pinfunction "1_1") (pintype "passive"))
    )
    (net (code "11") (name "Net-(CON1-+5V)") (class "Default")
      (node (ref "CON1") (pin "1") (pinfunction "+5V_1") (pintype "passive"))
      (node (ref "F1") (pin "1") (pinfunction "1_1") (pintype "passive"))
      (node (ref "F1") (pin "2") (pinfunction "1_2") (pintype "passive"))
    )
    (net (code "12") (name "Net-(CON10-+5V1)") (class "Default")
      (node (ref "CON10") (pin "4") (pinfunction "+5V1_4") (pintype "passive"))
      (node (ref "F12") (pin "1") (pinfunction "1_1") (pintype "bidirectional"))
    )
    (net (code "13") (name "Net-(CON10-+5V2)") (class "Default")
      (node (ref "CON10") (pin "6") (pinfunction "+5V2_6") (pintype "passive"))
      (node (ref "F13") (pin "1") (pinfunction "1_1") (pintype "bidirectional"))
    )
    (net (code "14") (name "Net-(CON10-+12V1)") (class "Default")
      (node (ref "CON10") (pin "1") (pinfunction "+12V1_1") (pintype "passive"))
      (node (ref "F15") (pin "1") (pinfunction "1_1") (pintype "bidirectional"))
    )
    (net (code "15") (name "Net-(CON10-+12V2)") (class "Default")
      (node (ref "CON10") (pin "3") (pinfunction "+12V2_3") (pintype "passive"))
      (node (ref "F14") (pin "1") (pinfunction "1_1") (pintype "bidirectional"))
    )
    (net (code "16") (name "Net-(CON11-+5V1)") (class "Default")
      (node (ref "CON11") (pin "4") (pinfunction "+5V1_4") (pintype "passive"))
      (node (ref "F16") (pin "1") (pinfunction "1_1") (pintype "bidirectional"))
    )
    (net (code "17") (name "Net-(CON11-+5V2)") (class "Default")
      (node (ref "CON11") (pin "6") (pinfunction "+5V2_6") (pintype "passive"))
      (node (ref "F17") (pin "1") (pinfunction "1_1") (pintype "bidirectional"))
    )
    (net (code "18") (name "Net-(CON11-+12V1)") (class "Default")
      (node (ref "CON11") (pin "1") (pinfunction "+12V1_1") (pintype "passive"))
      (node (ref "F19") (pin "1") (pinfunction "1_1") (pintype "bidirectional"))
    )
    (net (code "19") (name "Net-(CON11-+12V2)") (class "Default")
      (node (ref "CON11") (pin "3") (pinfunction "+12V2_3") (pintype "passive"))
      (node (ref "F18") (pin "1") (pinfunction "1_1") (pintype "bidirectional"))
    )
    (net (code "20") (name "Net-(CON12-+5V1)") (class "Default")
      (node (ref "CON12") (pin "4") (pinfunction "+5V1_4") (pintype "passive"))
      (node (ref "F20") (pin "1") (pinfunction "1_1") (pintype "bidirectional"))
    )
    (net (code "21") (name "Net-(CON12-+5V2)") (class "Default")
      (node (ref "CON12") (pin "6") (pinfunction "+5V2_6") (pintype "passive"))
      (node (ref "F21") (pin "1") (pinfunction "1_1") (pintype "bidirectional"))
    )
    (net (code "22") (name "Net-(CON12-+12V1)") (class "Default")
      (node (ref "CON12") (pin "1") (pinfunction "+12V1_1") (pintype "passive"))
      (node (ref "F23") (pin "1") (pinfunction "1_1") (pintype "bidirectional"))
    )
    (net (code "23") (name "Net-(CON12-+12V2)") (class "Default")
      (node (ref "CON12") (pin "3") (pinfunction "+12V2_3") (pintype "passive"))
      (node (ref "F22") (pin "1") (pinfunction "1_1") (pintype "bidirectional"))
    )
    (net (code "24") (name "Net-(CON13-+5V1)") (class "Default")
      (node (ref "CON13") (pin "4") (pinfunction "+5V1_4") (pintype "passive"))
      (node (ref "F24") (pin "1") (pinfunction "1_1") (pintype "bidirectional"))
    )
    (net (code "25") (name "Net-(CON13-+5V2)") (class "Default")
      (node (ref "CON13") (pin "6") (pinfunction "+5V2_6") (pintype "passive"))
      (node (ref "F25") (pin "1") (pinfunction "1_1") (pintype "bidirectional"))
    )
    (net (code "26") (name "Net-(CON13-+12V1)") (class "Default")
      (node (ref "CON13") (pin "1") (pinfunction "+12V1_1") (pintype "passive"))
      (node (ref "F27") (pin "1") (pinfunction "1_1") (pintype "bidirectional"))
    )
    (net (code "27") (name "Net-(CON13-+12V2)") (class "Default")
      (node (ref "CON13") (pin "3") (pinfunction "+12V2_3") (pintype "passive"))
      (node (ref "F26") (pin "1") (pinfunction "1_1") (pintype "bidirectional"))
    )
    (net (code "28") (name "Net-(CON14-+5V1)") (class "Default")
      (node (ref "CON14") (pin "4") (pinfunction "+5V1_4") (pintype "passive"))
      (node (ref "F28") (pin "1") (pinfunction "1_1") (pintype "bidirectional"))
    )
    (net (code "29") (name "Net-(CON14-+5V2)") (class "Default")
      (node (ref "CON14") (pin "6") (pinfunction "+5V2_6") (pintype "passive"))
      (node (ref "F29") (pin "1") (pinfunction "1_1") (pintype "bidirectional"))
    )
    (net (code "30") (name "Net-(CON14-+12V1)") (class "Default")
      (node (ref "CON14") (pin "1") (pinfunction "+12V1_1") (pintype "passive"))
      (node (ref "F31") (pin "1") (pinfunction "1_1") (pintype "bidirectional"))
    )
    (net (code "31") (name "Net-(CON14-+12V2)") (class "Default")
      (node (ref "CON14") (pin "3") (pinfunction "+12V2_3") (pintype "passive"))
      (node (ref "F30") (pin "1") (pinfunction "1_1") (pintype "bidirectional"))
    )
    (net (code "32") (name "Net-(CON16(FUSED)-+5V)") (class "Default")
      (node (ref "CON16(FUSED)") (pin "2") (pinfunction "+5V_2") (pintype "passive"))
      (node (ref "F6") (pin "1") (pinfunction "1_1") (pintype "bidirectional"))
    )
    (net (code "33") (name "Net-(CON16(FUSED)-+12V)") (class "Default")
      (node (ref "CON16(FUSED)") (pin "1") (pinfunction "+12V_1") (pintype "passive"))
      (node (ref "F4") (pin "1") (pinfunction "1_1") (pintype "bidirectional"))
    )
    (net (code "34") (name "Net-(CON17(FUSED)-+5V)") (class "Default")
      (node (ref "CON17(FUSED)") (pin "2") (pinfunction "+5V_2") (pintype "passive"))
      (node (ref "F7") (pin "1") (pinfunction "1_1") (pintype "bidirectional"))
    )
    (net (code "35") (name "Net-(CON17(FUSED)-+12V)") (class "Default")
      (node (ref "CON17(FUSED)") (pin "1") (pinfunction "+12V_1") (pintype "passive"))
      (node (ref "F5") (pin "1") (pinfunction "1_1") (pintype "bidirectional"))
    )
    (net (code "36") (name "Net-(CON17-+5V1)") (class "Default")
      (node (ref "CON17") (pin "4") (pinfunction "+5V1_4") (pintype "passive"))
      (node (ref "F8") (pin "1") (pinfunction "1_1") (pintype "bidirectional"))
    )
    (net (code "37") (name "Net-(CON17-+5V2)") (class "Default")
      (node (ref "CON17") (pin "6") (pinfunction "+5V2_6") (pintype "passive"))
      (node (ref "F9") (pin "1") (pinfunction "1_1") (pintype "bidirectional"))
    )
    (net (code "38") (name "Net-(CON17-+12V1)") (class "Default")
      (node (ref "CON17") (pin "1") (pinfunction "+12V1_1") (pintype "passive"))
      (node (ref "F11") (pin "1") (pinfunction "1_1") (pintype "bidirectional"))
    )
    (net (code "39") (name "Net-(CON17-+12V2)") (class "Default")
      (node (ref "CON17") (pin "3") (pinfunction "+12V2_3") (pintype "passive"))
      (node (ref "F10") (pin "1") (pinfunction "1_1") (pintype "bidirectional"))
    )
    (net (code "40") (name "Net-(IC1-IP+1)") (class "Default")
      (node (ref "F1") (pin "3") (pinfunction "2_3") (pintype "passive"))
      (node (ref "F1") (pin "4") (pinfunction "2_4") (pintype "passive"))
      (node (ref "IC1") (pin "1") (pinfunction "IP+1_1") (pintype "bidirectional"))
      (node (ref "IC1") (pin "2") (pinfunction "IP+2_2") (pintype "bidirectional"))
    )
    (net (code "41") (name "Net-(IC2-INPUT+)") (class "Default")
      (node (ref "C4") (pin "1") (pinfunction "1_1") (pintype "passive"))
      (node (ref "IC2") (pin "1") (pinfunction "REF_OUT_1") (pintype "bidirectional"))
      (node (ref "IC2") (pin "3") (pinfunction "INPUT+_3") (pintype "bidirectional"))
      (node (ref "IC2") (pin "8") (pinfunction "REF_FEEDBACK_8") (pintype "bidirectional"))
    )
    (net (code "42") (name "Net-(IC2-INPUT-)") (class "Default")
      (node (ref "IC2") (pin "2") (pinfunction "INPUT-_2") (pintype "bidirectional"))
      (node (ref "R3") (pin "1") (pinfunction "1_1") (pintype "passive"))
      (node (ref "R5") (pin "2") (pinfunction "WIPER_2") (pintype "passive"))
      (node (ref "R5") (pin "3") (pinfunction "CW_3") (pintype "passive"))
    )
    (net (code "43") (name "Net-(LED1-C)") (class "Default")
      (node (ref "LED1") (pin "2") (pinfunction "C_2") (pintype "passive"))
      (node (ref "R7") (pin "2") (pinfunction "2_2") (pintype "passive"))
    )
    (net (code "44") (name "Net-(LED2-C)") (class "Default")
      (node (ref "LED2") (pin "2") (pinfunction "C_2") (pintype "passive"))
      (node (ref "R12") (pin "2") (pinfunction "2_2") (pintype "passive"))
    )
    (net (code "45") (name "Net-(LED3-C)") (class "Default")
      (node (ref "LED3") (pin "2") (pinfunction "C_2") (pintype "passive"))
      (node (ref "R13") (pin "2") (pinfunction "2_2") (pintype "passive"))
    )
    (net (code "46") (name "Net-(MOD1-ON{slash}OFF)") (class "Default")
      (node (ref "CON6") (pin "2") (pinfunction "2_2") (pintype "passive"))
      (node (ref "MOD1") (pin "2") (pinfunction "ON/OFF_2") (pintype "bidirectional"))
    )
    (net (code "47") (name "Net-(MOD1-TRIM)") (class "Default")
      (node (ref "MOD1") (pin "6") (pinfunction "TRIM_6") (pintype "bidirectional"))
      (node (ref "R8") (pin "1") (pinfunction "1_1") (pintype "passive"))
    )
    (net (code "48") (name "Net-(MOD2-ON{slash}OFF)") (class "Default")
      (node (ref "CON8") (pin "2") (pinfunction "2_2") (pintype "passive"))
      (node (ref "MOD2") (pin "2") (pinfunction "ON/OFF_2") (pintype "bidirectional"))
    )
    (net (code "49") (name "Net-(MOD2-TRIM)") (class "Default")
      (node (ref "MOD2") (pin "6") (pinfunction "TRIM_6") (pintype "bidirectional"))
      (node (ref "R10") (pin "1") (pinfunction "1_1") (pintype "passive"))
    )
    (net (code "50") (name "Net-(Q1-G)") (class "Default")
      (node (ref "C1") (pin "2") (pinfunction "2_2") (pintype "passive"))
      (node (ref "D1") (pin "A") (pinfunction "A_A") (pintype "passive"))
      (node (ref "Q1") (pin "1") (pinfunction "G_1") (pintype "bidirectional"))
      (node (ref "R1") (pin "1") (pinfunction "1_1") (pintype "passive"))
      (node (ref "R2") (pin "2") (pinfunction "2_2") (pintype "passive"))
    )
    (net (code "51") (name "Net-(Q2-G)") (class "Default")
      (node (ref "C7") (pin "2") (pinfunction "2_2") (pintype "passive"))
      (node (ref "D4") (pin "A") (pinfunction "A_A") (pintype "passive"))
      (node (ref "Q2") (pin "1") (pinfunction "G_1") (pintype "bidirectional"))
      (node (ref "R4") (pin "1") (pinfunction "1_1") (pintype "passive"))
      (node (ref "R6") (pin "1") (pinfunction "1_1") (pintype "passive"))
    )
    (net (code "52") (name "Net-(R9-CCW)") (class "Default")
      (node (ref "R8") (pin "2") (pinfunction "2_2") (pintype "passive"))
      (node (ref "R9") (pin "1") (pinfunction "CCW_1") (pintype "passive"))
      (node (ref "R9") (pin "2") (pinfunction "WIPER_2") (pintype "passive"))
    )
    (net (code "53") (name "Net-(R11-CCW)") (class "Default")
      (node (ref "R10") (pin "2") (pinfunction "2_2") (pintype "passive"))
      (node (ref "R11") (pin "1") (pinfunction "CCW_1") (pintype "passive"))
      (node (ref "R11") (pin "2") (pinfunction "WIPER_2") (pintype "passive"))
    )
    (net (code "54") (name "REVERSE_PROT_OUT") (class "Default")
      (node (ref "C1") (pin "1") (pinfunction "1_1") (pintype "passive"))
      (node (ref "C5") (pin "1") (pinfunction "1_1") (pintype "passive"))
      (node (ref "C6") (pin "1") (pinfunction "1_1") (pintype "passive"))
      (node (ref "C7") (pin "1") (pinfunction "1_1") (pintype "passive"))
      (node (ref "D1") (pin "C") (pinfunction "C_C") (pintype "passive"))
      (node (ref "D3") (pin "C") (pinfunction "C_C") (pintype "passive"))
      (node (ref "D4") (pin "C") (pinfunction "C_C") (pintype "passive"))
      (node (ref "IC2") (pin "7") (pinfunction "SUPPLY+_7") (pintype "bidirectional"))
      (node (ref "Q1") (pin "3") (pinfunction "S_3") (pintype "bidirectional"))
      (node (ref "Q2") (pin "3") (pinfunction "S_3") (pintype "bidirectional"))
      (node (ref "R1") (pin "2") (pinfunction "2_2") (pintype "passive"))
      (node (ref "R3") (pin "2") (pinfunction "2_2") (pintype "passive"))
      (node (ref "R4") (pin "2") (pinfunction "2_2") (pintype "passive"))
    )
    (net (code "55") (name "VIN") (class "Default")
      (node (ref "C10") (pin "1") (pinfunction "1_1") (pintype "passive"))
      (node (ref "C11") (pin "1") (pinfunction "1_1") (pintype "passive"))
      (node (ref "C12") (pin "1") (pinfunction "1_1") (pintype "passive"))
      (node (ref "C25") (pin "+") (pinfunction "+_+") (pintype "passive"))
      (node (ref "C26") (pin "+") (pinfunction "+_+") (pintype "passive"))
      (node (ref "C27") (pin "1") (pinfunction "1_1") (pintype "passive"))
      (node (ref "C28") (pin "1") (pinfunction "1_1") (pintype "passive"))
      (node (ref "C29") (pin "1") (pinfunction "1_1") (pintype "passive"))
      (node (ref "C30") (pin "1") (pinfunction "1_1") (pintype "passive"))
      (node (ref "C8") (pin "1") (pinfunction "1_1") (pintype "passive"))
      (node (ref "C9") (pin "1") (pinfunction "1_1") (pintype "passive"))
      (node (ref "CON18") (pin "3") (pinfunction "3_3") (pintype "passive"))
      (node (ref "CON2") (pin "1") (pinfunction "1_1") (pintype "passive"))
      (node (ref "D6") (pin "C") (pinfunction "C_C") (pintype "passive"))
      (node (ref "LED1") (pin "1") (pinfunction "A_1") (pintype "passive"))
      (node (ref "MOD1") (pin "1") (pinfunction "VIN_1") (pintype "bidirectional"))
      (node (ref "MOD2") (pin "1") (pinfunction "VIN_1") (pintype "bidirectional"))
      (node (ref "Q2") (pin "2") (pinfunction "D_2") (pintype "bidirectional"))
    )
    (net (code "56") (name "unconnected-(IC2-BALANCE-Pad5)") (class "Default")
      (node (ref "IC2") (pin "5") (pinfunction "BALANCE_5") (pintype "bidirectional"))
    )
    (net (code "57") (name "unconnected-(MOD1-POWER_GOOD-Pad5)") (class "Default")
      (node (ref "MOD1") (pin "5") (pinfunction "POWER_GOOD_5") (pintype "bidirectional"))
    )
    (net (code "58") (name "unconnected-(MOD2-POWER_GOOD-Pad5)") (class "Default")
      (node (ref "MOD2") (pin "5") (pinfunction "POWER_GOOD_5") (pintype "bidirectional"))
    )
    (net (code "59") (name "~{OUTPUT_ENABLED}") (class "Default")
      (node (ref "IC2") (pin "6") (pinfunction "OUTPUT_6") (pintype "bidirectional"))
      (node (ref "R6") (pin "2") (pinfunction "2_2") (pintype "passive"))
    )
  )
)
